# 3w-rgb-led-connector-mk-5_0.net
KiCad netlist of a schematic drawn in EAGLE
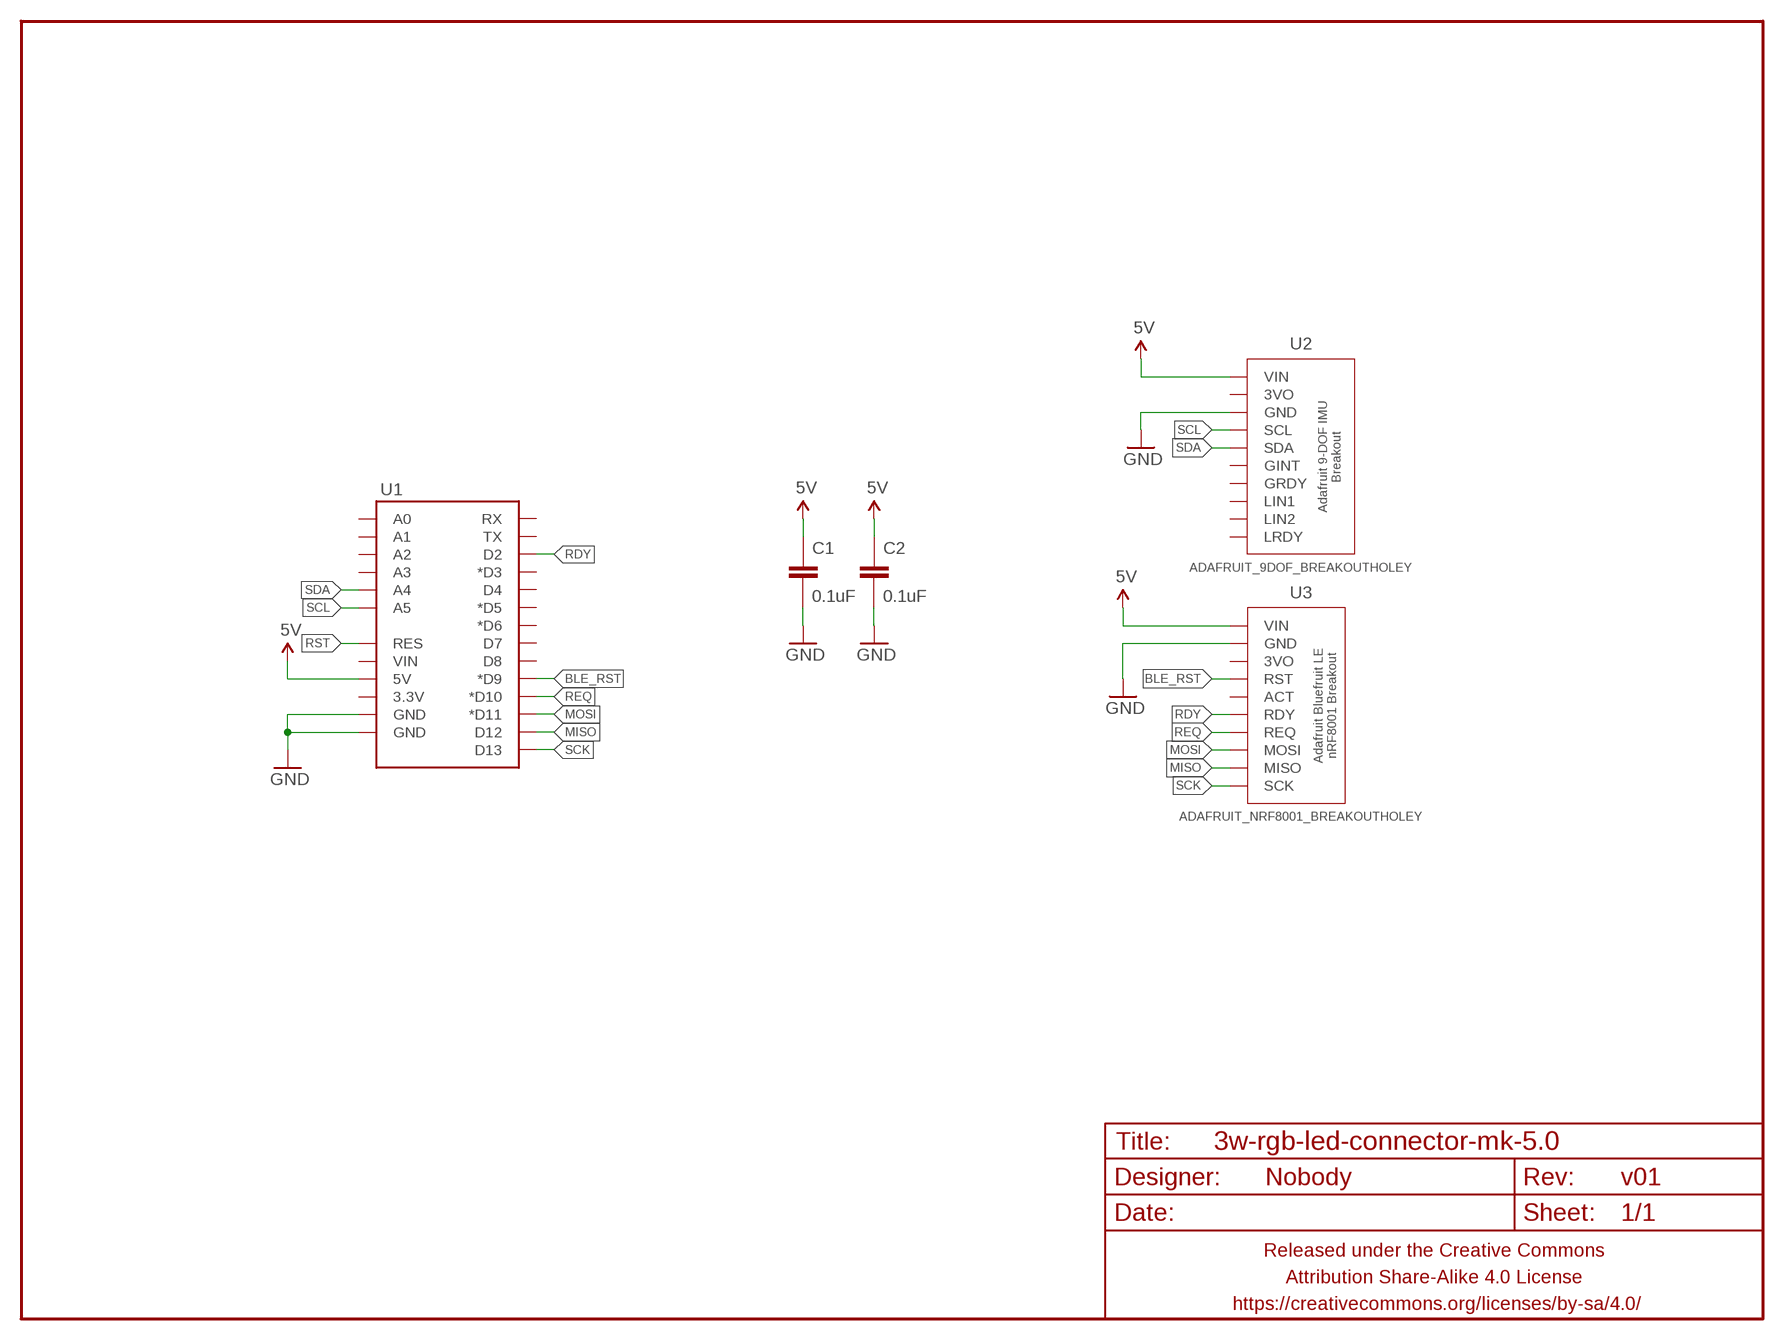
[diagram p0: schematic, sheet 1]

(export (version "E")
  (design (tool "Eeschema 10.0.6"))
  (components
    (comp (ref "C1")
      (value "0.1uF")
      (footprint "eagle-import:C025-024X044")
      (libsource (lib "eagle-import") (part "CAPACITOR-CERAMIC025-024X044"))
    )
    (comp (ref "C2")
      (value "0.1uF")
      (footprint "eagle-import:C025-024X044")
      (libsource (lib "eagle-import") (part "CAPACITOR-CERAMIC025-024X044"))
    )
    (comp (ref "FRAME1")
      (value "FRAME-LETTERNO_PACKAGE")
      (footprint "eagle-import:DUMMY")
      (fields (field (name "DESIGNER") "Nobody"))
      (libsource (lib "eagle-import") (part "FRAME-LETTERNO_PACKAGE"))
    )
    (comp (ref "U1")
      (value "ARDUINO_SHIELD_SMALLER")
      (footprint "eagle-import:ARDUINO_SHIELD_NOOUTLINE_INSIDE_SMALLER")
      (libsource (lib "eagle-import") (part "ARDUINO_SHIELD_SMALLER"))
    )
    (comp (ref "U2")
      (value "ADAFRUIT_9DOF_BREAKOUTHOLEY")
      (footprint "eagle-import:ADAFRUIT_9DOF_BREAKOUT_HOLEY")
      (libsource (lib "eagle-import") (part "ADAFRUIT_9DOF_BREAKOUTHOLEY"))
    )
    (comp (ref "U3")
      (value "ADAFRUIT_NRF8001_BREAKOUTHOLEY")
      (footprint "eagle-import:ADAFRUIT_NRF8001_HOLEY")
      (libsource (lib "eagle-import") (part "ADAFRUIT_NRF8001_BREAKOUTHOLEY"))
    )
  )
  (nets
    (net (code "1") (name "5V") (class "Default")
      (node (ref "C1") (pin "1") (pinfunction "1_1") (pintype "passive"))
      (node (ref "C2") (pin "1") (pinfunction "1_1") (pintype "passive"))
      (node (ref "U1") (pin "5V") (pinfunction "5V_5V") (pintype "bidirectional"))
      (node (ref "U2") (pin "VIN") (pinfunction "VIN_VIN") (pintype "bidirectional"))
      (node (ref "U3") (pin "VIN") (pinfunction "VIN_VIN") (pintype "bidirectional"))
    )
    (net (code "2") (name "BLE_RST") (class "Default")
      (node (ref "U1") (pin "D9") (pinfunction "*D9_D9") (pintype "bidirectional"))
      (node (ref "U3") (pin "RST") (pinfunction "RST_RST") (pintype "bidirectional"))
    )
    (net (code "3") (name "GND") (class "Default")
      (node (ref "C1") (pin "2") (pinfunction "2_2") (pintype "passive"))
      (node (ref "C2") (pin "2") (pinfunction "2_2") (pintype "passive"))
      (node (ref "U1") (pin "GND@0") (pinfunction "GND_GND@0") (pintype "bidirectional"))
      (node (ref "U1") (pin "GND@1") (pinfunction "GND_GND@1") (pintype "bidirectional"))
      (node (ref "U2") (pin "GND") (pinfunction "GND_GND") (pintype "bidirectional"))
      (node (ref "U3") (pin "GND") (pinfunction "GND_GND") (pintype "bidirectional"))
    )
    (net (code "4") (name "MISO") (class "Default")
      (node (ref "U1") (pin "D12") (pinfunction "D12_D12") (pintype "bidirectional"))
      (node (ref "U3") (pin "MISO") (pinfunction "MISO_MISO") (pintype "bidirectional"))
    )
    (net (code "5") (name "MOSI") (class "Default")
      (node (ref "U1") (pin "D11") (pinfunction "*D11_D11") (pintype "bidirectional"))
      (node (ref "U3") (pin "MOSI") (pinfunction "MOSI_MOSI") (pintype "bidirectional"))
    )
    (net (code "6") (name "RDY") (class "Default")
      (node (ref "U1") (pin "D2") (pinfunction "D2_D2") (pintype "bidirectional"))
      (node (ref "U3") (pin "RDY") (pinfunction "RDY_RDY") (pintype "bidirectional"))
    )
    (net (code "7") (name "REQ") (class "Default")
      (node (ref "U1") (pin "D10") (pinfunction "*D10_D10") (pintype "bidirectional"))
      (node (ref "U3") (pin "REQ") (pinfunction "REQ_REQ") (pintype "bidirectional"))
    )
    (net (code "8") (name "RST") (class "Default")
      (node (ref "U1") (pin "RES") (pinfunction "RES_RES") (pintype "bidirectional"))
    )
    (net (code "9") (name "SCK") (class "Default")
      (node (ref "U1") (pin "D13") (pinfunction "D13_D13") (pintype "bidirectional"))
      (node (ref "U3") (pin "SCK") (pinfunction "SCK_SCK") (pintype "bidirectional"))
    )
    (net (code "10") (name "SCL") (class "Default")
      (node (ref "U1") (pin "A5") (pinfunction "A5_A5") (pintype "bidirectional"))
      (node (ref "U2") (pin "SCL") (pinfunction "SCL_SCL") (pintype "bidirectional"))
    )
    (net (code "11") (name "SDA") (class "Default")
      (node (ref "U1") (pin "A4") (pinfunction "A4_A4") (pintype "bidirectional"))
      (node (ref "U2") (pin "SDA") (pinfunction "SDA_SDA") (pintype "bidirectional"))
    )
    (net (code "12") (name "unconnected-(U1-*D3-PadD3)") (class "Default")
      (node (ref "U1") (pin "D3") (pinfunction "*D3_D3") (pintype "bidirectional"))
    )
    (net (code "13") (name "unconnected-(U1-*D5-PadD5)") (class "Default")
      (node (ref "U1") (pin "D5") (pinfunction "*D5_D5") (pintype "bidirectional"))
    )
    (net (code "14") (name "unconnected-(U1-*D6-PadD6)") (class "Default")
      (node (ref "U1") (pin "D6") (pinfunction "*D6_D6") (pintype "bidirectional"))
    )
    (net (code "15") (name "unconnected-(U1-Pad3.3V)") (class "Default")
      (node (ref "U1") (pin "3.3V") (pinfunction "3.3V_3.3V") (pintype "bidirectional"))
    )
    (net (code "16") (name "unconnected-(U1-PadA0)") (class "Default")
      (node (ref "U1") (pin "A0") (pinfunction "A0_A0") (pintype "bidirectional"))
    )
    (net (code "17") (name "unconnected-(U1-PadA1)") (class "Default")
      (node (ref "U1") (pin "A1") (pinfunction "A1_A1") (pintype "bidirectional"))
    )
    (net (code "18") (name "unconnected-(U1-PadA2)") (class "Default")
      (node (ref "U1") (pin "A2") (pinfunction "A2_A2") (pintype "bidirectional"))
    )
    (net (code "19") (name "unconnected-(U1-PadA3)") (class "Default")
      (node (ref "U1") (pin "A3") (pinfunction "A3_A3") (pintype "bidirectional"))
    )
    (net (code "20") (name "unconnected-(U1-PadD4)") (class "Default")
      (node (ref "U1") (pin "D4") (pinfunction "D4_D4") (pintype "bidirectional"))
    )
    (net (code "21") (name "unconnected-(U1-PadD7)") (class "Default")
      (node (ref "U1") (pin "D7") (pinfunction "D7_D7") (pintype "bidirectional"))
    )
    (net (code "22") (name "unconnected-(U1-PadD8)") (class "Default")
      (node (ref "U1") (pin "D8") (pinfunction "D8_D8") (pintype "bidirectional"))
    )
    (net (code "23") (name "unconnected-(U1-PadRX)") (class "Default")
      (node (ref "U1") (pin "RX") (pinfunction "RX_RX") (pintype "bidirectional"))
    )
    (net (code "24") (name "unconnected-(U1-PadTX)") (class "Default")
      (node (ref "U1") (pin "TX") (pinfunction "TX_TX") (pintype "bidirectional"))
    )
    (net (code "25") (name "unconnected-(U1-PadVIN)") (class "Default")
      (node (ref "U1") (pin "VIN") (pinfunction "VIN_VIN") (pintype "bidirectional"))
    )
    (net (code "26") (name "unconnected-(U2-Pad3VO)") (class "Default")
      (node (ref "U2") (pin "3VO") (pinfunction "3VO_3VO") (pintype "bidirectional"))
    )
    (net (code "27") (name "unconnected-(U2-PadGINT)") (class "Default")
      (node (ref "U2") (pin "GINT") (pinfunction "GINT_GINT") (pintype "bidirectional"))
    )
    (net (code "28") (name "unconnected-(U2-PadGRDY)") (class "Default")
      (node (ref "U2") (pin "GRDY") (pinfunction "GRDY_GRDY") (pintype "bidirectional"))
    )
    (net (code "29") (name "unconnected-(U2-PadLIN1)") (class "Default")
      (node (ref "U2") (pin "LIN1") (pinfunction "LIN1_LIN1") (pintype "bidirectional"))
    )
    (net (code "30") (name "unconnected-(U2-PadLIN2)") (class "Default")
      (node (ref "U2") (pin "LIN2") (pinfunction "LIN2_LIN2") (pintype "bidirectional"))
    )
    (net (code "31") (name "unconnected-(U2-PadLRDY)") (class "Default")
      (node (ref "U2") (pin "LRDY") (pinfunction "LRDY_LRDY") (pintype "bidirectional"))
    )
    (net (code "32") (name "unconnected-(U3-Pad3VO)") (class "Default")
      (node (ref "U3") (pin "3VO") (pinfunction "3VO_3VO") (pintype "bidirectional"))
    )
    (net (code "33") (name "unconnected-(U3-PadACT)") (class "Default")
      (node (ref "U3") (pin "ACT") (pinfunction "ACT_ACT") (pintype "bidirectional"))
    )
  )
)
